# Sheet1.net
KiCad netlist of a schematic drawn in Altium Designer
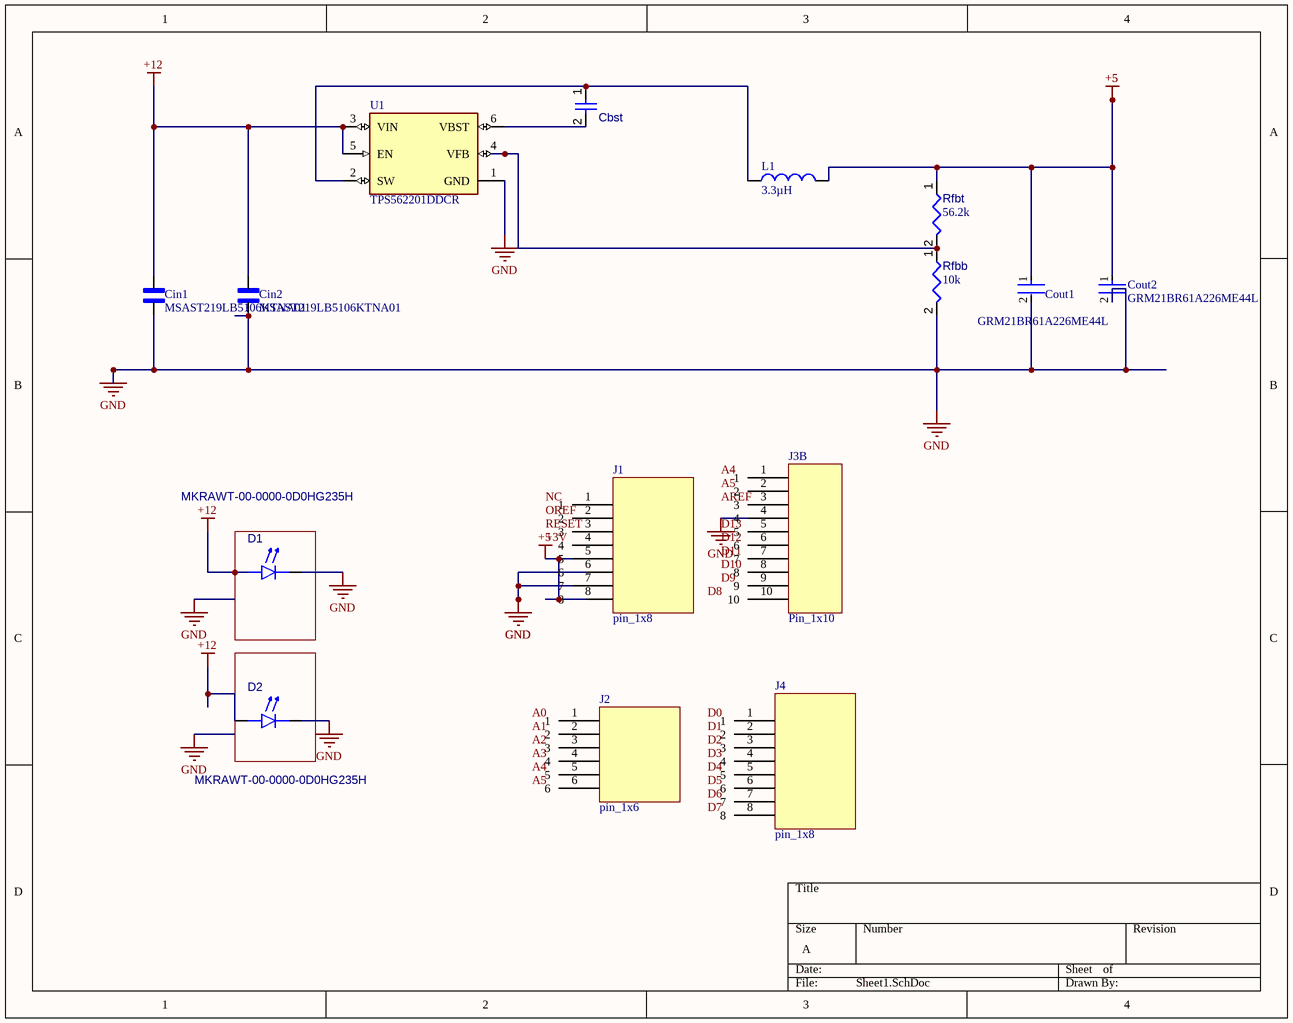
[diagram p0: Sheet1.SchDoc]

(export (version "E")
  (design (tool "Eeschema 10.0.6"))
  (components
    (comp (ref "Cbst") (value "AVX 08053C104KAT2A") (libsource (lib "Eshwari Pardeshi") (part "CAP-NP-2")))
    (comp (ref "Cin1")
      (value "MSAST219LB5106KTNA01")
      (footprint "CAPC2012X95N")
      (fields (field (name "MF") "{'manufacturer': u'Taiyo Yuden'}"))
      (libsource (lib "MSAST219LB5106KTNA01") (part "MSAST219LB5106KTNA01"))
    )
    (comp (ref "Cin2")
      (value "MSAST219LB5106KTNA01")
      (footprint "CAPC2012X95N")
      (fields (field (name "MF") "{'manufacturer': u'Taiyo Yuden'}"))
      (libsource (lib "MSAST219LB5106KTNA01") (part "MSAST219LB5106KTNA01"))
    )
    (comp (ref "Cout1")
      (value "GRM21BR61A226ME44L")
      (footprint "FP-GRM21B-0_2-e0_2_0_7-IPC_C")
      (description "Chip Multilayer Ceramic Capacitors for General Purpose, 0805, 22uF, X5R, 15%, 20%, 10V")
      (fields (field (name "TOLERANCE") "20%") (field (name "VOLTAGE") "10V"))
      (libsource (lib "Altium Content Vault") (part "b4654b650e69147ec39a6b967a45e02"))
    )
    (comp (ref "Cout2")
      (value "GRM21BR61A226ME44L")
      (footprint "FP-GRM21B-0_2-e0_2_0_7-IPC_C")
      (description "Chip Multilayer Ceramic Capacitors for General Purpose, 0805, 22uF, X5R, 15%, 20%, 10V")
      (fields (field (name "TOLERANCE") "20%") (field (name "VOLTAGE") "10V"))
      (libsource (lib "Altium Content Vault") (part "b4654b650e69147ec39a6b967a45e02"))
    )
    (comp (ref "D1")
      (value "MKRAWT-00-0000-0D0HG235H")
      (description "Single Color LED, Neutral White, 6.5mm")
      (libsource (lib "Eshwari Pardeshi") (part "DIODE-LED-2"))
    )
    (comp (ref "D2")
      (value "MKRAWT-00-0000-0D0HG235H")
      (description "Single Color LED, Neutral White, 6.5mm")
      (libsource (lib "Eshwari Pardeshi") (part "DIODE-LED-2"))
    )
    (comp (ref "J1")
      (value "pin_1x8")
      (footprint "Pin_1x8_2.54mm")
      (libsource (lib "ardino header pins") (part "pin_1x8"))
    )
    (comp (ref "J2")
      (value "pin_1x6")
      (footprint "Pin1x6_2.54mm")
      (libsource (lib "ardino header pins") (part "pin_1x6"))
    )
    (comp (ref "J3")
      (value "Pin_1x10")
      (footprint "Pin_1x10_2.54mm")
      (libsource (lib "ardino header pins") (part "Pin_1x10"))
    )
    (comp (ref "J4")
      (value "pin_1x8")
      (footprint "Pin_1x8_2.54mm")
      (libsource (lib "ardino header pins") (part "pin_1x8"))
    )
    (comp (ref "L1")
      (value "3.3µH")
      (description "Inductor Power Unshielded Wirewound 3.3uH 20% 100KHz 2A 0.07Ohm DCR T/R")
      (fields (field (name "TOLERANCE") "20%") (field (name "Comment") "NPI43C3R3MTRF"))
      (libsource (lib "Eshwari Pardeshi") (part "IND-2"))
    )
    (comp (ref "Rfbb")
      (value "10k")
      (description "Res Thick Film 0201 10K Ohm 1% 0.05W(1/20W) ±200ppm/C Pad SMD T/R")
      (fields (field (name "TOLERANCE") "1%") (field (name "Comment") "RC0201FR-0710KL"))
      (libsource (lib "Eshwari Pardeshi") (part "RES-2"))
    )
    (comp (ref "Rfbt")
      (value "56.2k")
      (description "Res Thick Film 0201 56.2K Ohm 1% 0.05W(1/20W) ±200ppm/C Pad SMD T/R")
      (fields (field (name "TOLERANCE") "1%") (field (name "Comment") "RC0201FR-0756K2L"))
      (libsource (lib "Eshwari Pardeshi") (part "RES-2"))
    )
    (comp (ref "U1")
      (value "TPS562201DDCR")
      (footprint "FP-DDC0006A-IPC_C")
      (description "IC REG BUCK ADJ 2A TSOT23-6")
      (libsource (lib "Altium Content Vault") (part "957e164956730ea4bf6293280af19fc"))
    )
  )
  (nets
    (net (code "1") (name "+5") (class "Default")
      (node (ref "Cout1") (pin "1") (pinfunction "1_1") (pintype "passive"))
      (node (ref "Cout2") (pin "1") (pinfunction "1_1") (pintype "passive"))
      (node (ref "L1") (pin "2") (pinfunction "2_2") (pintype "passive"))
      (node (ref "Rfbt") (pin "1") (pinfunction "1_1") (pintype "passive"))
    )
    (net (code "2") (name "+12") (class "Default")
      (node (ref "Cin1") (pin "2") (pinfunction "2_2") (pintype "passive"))
      (node (ref "Cin2") (pin "2") (pinfunction "2_2") (pintype "passive"))
      (node (ref "D1") (pin "2") (pinfunction "A_2") (pintype "passive"))
      (node (ref "D2") (pin "2") (pinfunction "A_2") (pintype "passive"))
      (node (ref "U1") (pin "3") (pinfunction "VIN_3") (pintype "bidirectional"))
      (node (ref "U1") (pin "5") (pinfunction "EN_5") (pintype "input"))
    )
    (net (code "28") (name "GND") (class "Default")
      (node (ref "Cin1") (pin "1") (pinfunction "1_1") (pintype "passive"))
      (node (ref "Cin2") (pin "1") (pinfunction "1_1") (pintype "passive"))
      (node (ref "Cout1") (pin "2") (pinfunction "2_2") (pintype "passive"))
      (node (ref "Cout2") (pin "2") (pinfunction "2_2") (pintype "passive"))
      (node (ref "D1") (pin "1") (pinfunction "K_1") (pintype "passive"))
      (node (ref "D2") (pin "1") (pinfunction "K_1") (pintype "passive"))
      (node (ref "Rfbb") (pin "2") (pinfunction "2_2") (pintype "passive"))
      (node (ref "U1") (pin "1") (pinfunction "GND_1") (pintype "power_in"))
    )
    (net (code "29") (name "Net-(U1-SW)") (class "Default")
      (node (ref "Cbst") (pin "1") (pinfunction "1_1") (pintype "passive"))
      (node (ref "L1") (pin "1") (pinfunction "1_1") (pintype "passive"))
      (node (ref "U1") (pin "2") (pinfunction "SW_2") (pintype "bidirectional"))
    )
    (net (code "30") (name "Net-(U1-VBST)") (class "Default")
      (node (ref "Cbst") (pin "2") (pinfunction "2_2") (pintype "passive"))
      (node (ref "U1") (pin "6") (pinfunction "VBST_6") (pintype "bidirectional"))
    )
    (net (code "31") (name "Net-(U1-VFB)") (class "Default")
      (node (ref "Rfbb") (pin "1") (pinfunction "1_1") (pintype "passive"))
      (node (ref "Rfbt") (pin "2") (pinfunction "2_2") (pintype "passive"))
      (node (ref "U1") (pin "4") (pinfunction "VFB_4") (pintype "bidirectional"))
    )
    (net (code "32") (name "unconnected-(J1-Pad1)") (class "Default")
      (node (ref "J1") (pin "1") (pinfunction "1_1") (pintype "passive"))
    )
    (net (code "33") (name "unconnected-(J1-Pad2)") (class "Default")
      (node (ref "J1") (pin "2") (pinfunction "2_2") (pintype "passive"))
    )
    (net (code "34") (name "unconnected-(J1-Pad3)") (class "Default")
      (node (ref "J1") (pin "3") (pinfunction "3_3") (pintype "passive"))
    )
    (net (code "35") (name "unconnected-(J1-Pad4)") (class "Default")
      (node (ref "J1") (pin "4") (pinfunction "4_4") (pintype "passive"))
    )
    (net (code "36") (name "unconnected-(J1-Pad5)") (class "Default")
      (node (ref "J1") (pin "5") (pinfunction "5_5") (pintype "passive"))
    )
    (net (code "37") (name "unconnected-(J1-Pad6)") (class "Default")
      (node (ref "J1") (pin "6") (pinfunction "6_6") (pintype "passive"))
    )
    (net (code "38") (name "unconnected-(J1-Pad7)") (class "Default")
      (node (ref "J1") (pin "7") (pinfunction "7_7") (pintype "passive"))
    )
    (net (code "39") (name "unconnected-(J1-Pad8)") (class "Default")
      (node (ref "J1") (pin "8") (pinfunction "8_8") (pintype "passive"))
    )
    (net (code "40") (name "unconnected-(J2-Pad1)") (class "Default")
      (node (ref "J2") (pin "1") (pinfunction "1_1") (pintype "passive"))
    )
    (net (code "41") (name "unconnected-(J2-Pad2)") (class "Default")
      (node (ref "J2") (pin "2") (pinfunction "2_2") (pintype "passive"))
    )
    (net (code "42") (name "unconnected-(J2-Pad3)") (class "Default")
      (node (ref "J2") (pin "3") (pinfunction "3_3") (pintype "passive"))
    )
    (net (code "43") (name "unconnected-(J2-Pad4)") (class "Default")
      (node (ref "J2") (pin "4") (pinfunction "4_4") (pintype "passive"))
    )
    (net (code "44") (name "unconnected-(J2-Pad5)") (class "Default")
      (node (ref "J2") (pin "5") (pinfunction "5_5") (pintype "passive"))
    )
    (net (code "45") (name "unconnected-(J2-Pad6)") (class "Default")
      (node (ref "J2") (pin "6") (pinfunction "6_6") (pintype "passive"))
    )
    (net (code "46") (name "unconnected-(J3-Pad1)") (class "Default")
      (node (ref "J3") (pin "1") (pinfunction "1_1") (pintype "passive"))
    )
    (net (code "47") (name "unconnected-(J3-Pad2)") (class "Default")
      (node (ref "J3") (pin "2") (pinfunction "2_2") (pintype "passive"))
    )
    (net (code "48") (name "unconnected-(J3-Pad3)") (class "Default")
      (node (ref "J3") (pin "3") (pinfunction "3_3") (pintype "passive"))
    )
    (net (code "49") (name "unconnected-(J3-Pad4)") (class "Default")
      (node (ref "J3") (pin "4") (pinfunction "4_4") (pintype "passive"))
    )
    (net (code "50") (name "unconnected-(J3-Pad5)") (class "Default")
      (node (ref "J3") (pin "5") (pinfunction "5_5") (pintype "passive"))
    )
    (net (code "51") (name "unconnected-(J3-Pad6)") (class "Default")
      (node (ref "J3") (pin "6") (pinfunction "6_6") (pintype "passive"))
    )
    (net (code "52") (name "unconnected-(J3-Pad7)") (class "Default")
      (node (ref "J3") (pin "7") (pinfunction "7_7") (pintype "passive"))
    )
    (net (code "53") (name "unconnected-(J3-Pad8)") (class "Default")
      (node (ref "J3") (pin "8") (pinfunction "8_8") (pintype "passive"))
    )
    (net (code "54") (name "unconnected-(J3-Pad9)") (class "Default")
      (node (ref "J3") (pin "9") (pinfunction "9_9") (pintype "passive"))
    )
    (net (code "55") (name "unconnected-(J3-Pad10)") (class "Default")
      (node (ref "J3") (pin "10") (pinfunction "10_10") (pintype "passive"))
    )
    (net (code "56") (name "unconnected-(J4-Pad1)") (class "Default")
      (node (ref "J4") (pin "1") (pinfunction "1_1") (pintype "passive"))
    )
    (net (code "57") (name "unconnected-(J4-Pad2)") (class "Default")
      (node (ref "J4") (pin "2") (pinfunction "2_2") (pintype "passive"))
    )
    (net (code "58") (name "unconnected-(J4-Pad3)") (class "Default")
      (node (ref "J4") (pin "3") (pinfunction "3_3") (pintype "passive"))
    )
    (net (code "59") (name "unconnected-(J4-Pad4)") (class "Default")
      (node (ref "J4") (pin "4") (pinfunction "4_4") (pintype "passive"))
    )
    (net (code "60") (name "unconnected-(J4-Pad5)") (class "Default")
      (node (ref "J4") (pin "5") (pinfunction "5_5") (pintype "passive"))
    )
    (net (code "61") (name "unconnected-(J4-Pad6)") (class "Default")
      (node (ref "J4") (pin "6") (pinfunction "6_6") (pintype "passive"))
    )
    (net (code "62") (name "unconnected-(J4-Pad7)") (class "Default")
      (node (ref "J4") (pin "7") (pinfunction "7_7") (pintype "passive"))
    )
    (net (code "63") (name "unconnected-(J4-Pad8)") (class "Default")
      (node (ref "J4") (pin "8") (pinfunction "8_8") (pintype "passive"))
    )
  )
)
